# ProPrj_332G_2025-04-08_13-48-16_2025-05-.net
KiCad netlist of a schematic drawn in EasyEDA Pro
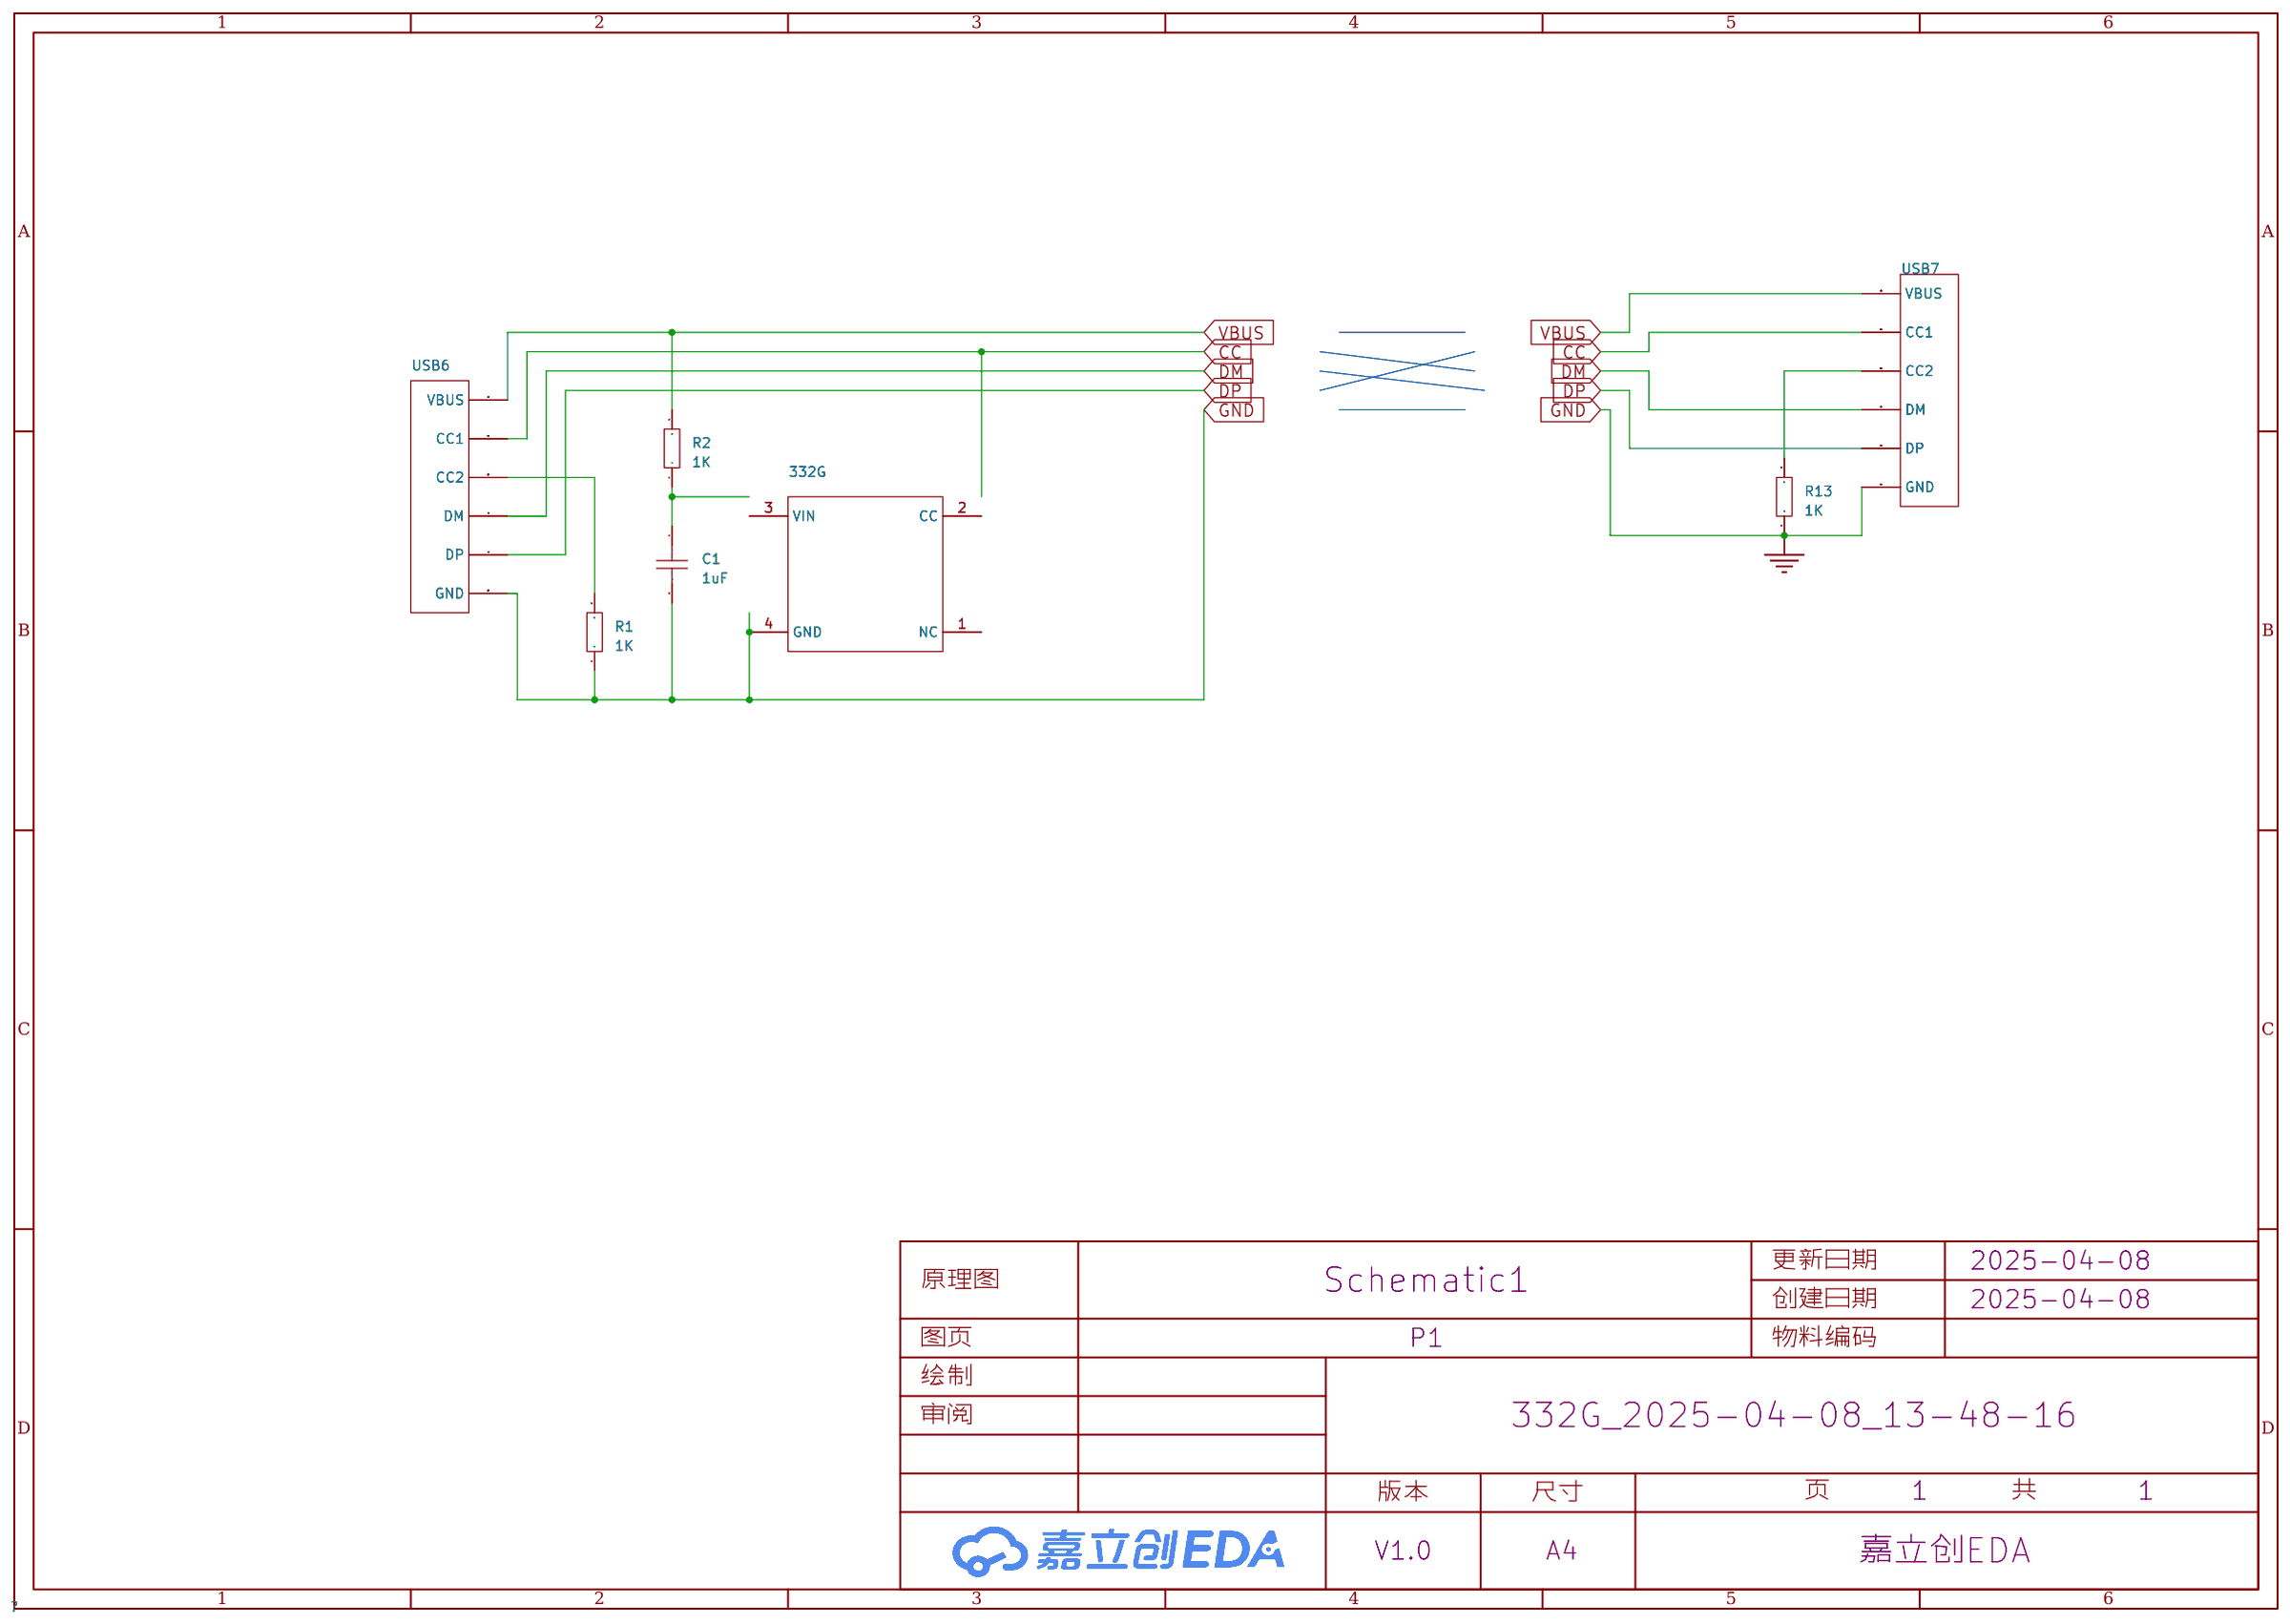
[diagram p0: schematic sheet]

(export (version "E")
  (design (tool "Eeschema 10.0.6"))
  (components
    (comp (ref "332G")
      (value "~")
      (footprint "easyedapro:ODFN-4_L1.6-W1.6")
      (libsource (lib "easyedapro") (part "332G"))
    )
    (comp (ref "C1")
      (value "1uF")
      (footprint "easyedapro:0603C")
      (libsource (lib "easyedapro") (part "0603C"))
    )
    (comp (ref "R1") (value "1K") (footprint "easyedapro:0603R") (libsource (lib "easyedapro") (part "10K")))
    (comp (ref "R2") (value "1K") (footprint "easyedapro:R0603") (libsource (lib "easyedapro") (part "电阻")))
    (comp (ref "R13") (value "1K") (footprint "easyedapro:0603R") (libsource (lib "easyedapro") (part "10K")))
    (comp (ref "USB6")
      (value "~")
      (footprint "easyedapro:TYPE-C14P")
      (libsource (lib "easyedapro") (part "TYPEC-14PIN(公头）"))
    )
    (comp (ref "USB7")
      (value "~")
      (footprint "easyedapro:TYPE-C14P")
      (libsource (lib "easyedapro") (part "TYPEC-14PIN(公头）"))
    )
  )
  (nets
    (net (code "1") (name "CC") (class "Default")
      (node (ref "USB6") (pin "CC1") (pinfunction "CC1_CC1") (pintype "unspecified"))
      (node (ref "USB7") (pin "CC1") (pinfunction "CC1_CC1") (pintype "unspecified"))
    )
    (net (code "2") (name "DM") (class "Default")
      (node (ref "USB6") (pin "DM") (pinfunction "DM_DM") (pintype "unspecified"))
      (node (ref "USB7") (pin "DM") (pinfunction "DM_DM") (pintype "unspecified"))
    )
    (net (code "3") (name "DP") (class "Default")
      (node (ref "USB6") (pin "DP") (pinfunction "DP_DP") (pintype "unspecified"))
      (node (ref "USB7") (pin "DP") (pinfunction "DP_DP") (pintype "unspecified"))
    )
    (net (code "4") (name "GND") (class "Default")
      (node (ref "332G") (pin "4") (pinfunction "GND_4") (pintype "input"))
      (node (ref "C1") (pin "2") (pinfunction "2_2") (pintype "input"))
      (node (ref "R1") (pin "1") (pinfunction "1_1") (pintype "input"))
      (node (ref "R13") (pin "1") (pinfunction "1_1") (pintype "input"))
      (node (ref "USB6") (pin "GND") (pinfunction "GND_GND") (pintype "unspecified"))
      (node (ref "USB7") (pin "GND") (pinfunction "GND_GND") (pintype "unspecified"))
    )
    (net (code "5") (name "Net-(C1-Pad1)") (class "Default")
      (node (ref "C1") (pin "1") (pinfunction "1_1") (pintype "input"))
      (node (ref "R2") (pin "1") (pinfunction "1_1") (pintype "input"))
    )
    (net (code "6") (name "Net-(R1-Pad2)") (class "Default")
      (node (ref "R1") (pin "2") (pinfunction "2_2") (pintype "input"))
      (node (ref "USB6") (pin "CC2") (pinfunction "CC2_CC2") (pintype "unspecified"))
    )
    (net (code "7") (name "Net-(R13-Pad2)") (class "Default")
      (node (ref "R13") (pin "2") (pinfunction "2_2") (pintype "input"))
      (node (ref "USB7") (pin "CC2") (pinfunction "CC2_CC2") (pintype "unspecified"))
    )
    (net (code "8") (name "VBUS") (class "Default")
      (node (ref "R2") (pin "2") (pinfunction "2_2") (pintype "input"))
      (node (ref "USB6") (pin "VBUS") (pinfunction "VBUS_VBUS") (pintype "unspecified"))
      (node (ref "USB7") (pin "VBUS") (pinfunction "VBUS_VBUS") (pintype "unspecified"))
    )
    (net (code "9") (name "unconnected-(332G-CC-Pad2)") (class "Default")
      (node (ref "332G") (pin "2") (pinfunction "CC_2") (pintype "input"))
    )
    (net (code "10") (name "unconnected-(332G-NC-Pad1)") (class "Default")
      (node (ref "332G") (pin "1") (pinfunction "NC_1") (pintype "input"))
    )
    (net (code "11") (name "unconnected-(332G-VIN-Pad3)") (class "Default")
      (node (ref "332G") (pin "3") (pinfunction "VIN_3") (pintype "input"))
    )
  )
)
